# Protoboard_MX2-7-6-Terminal.net
KiCad netlist of a schematic drawn in EAGLE
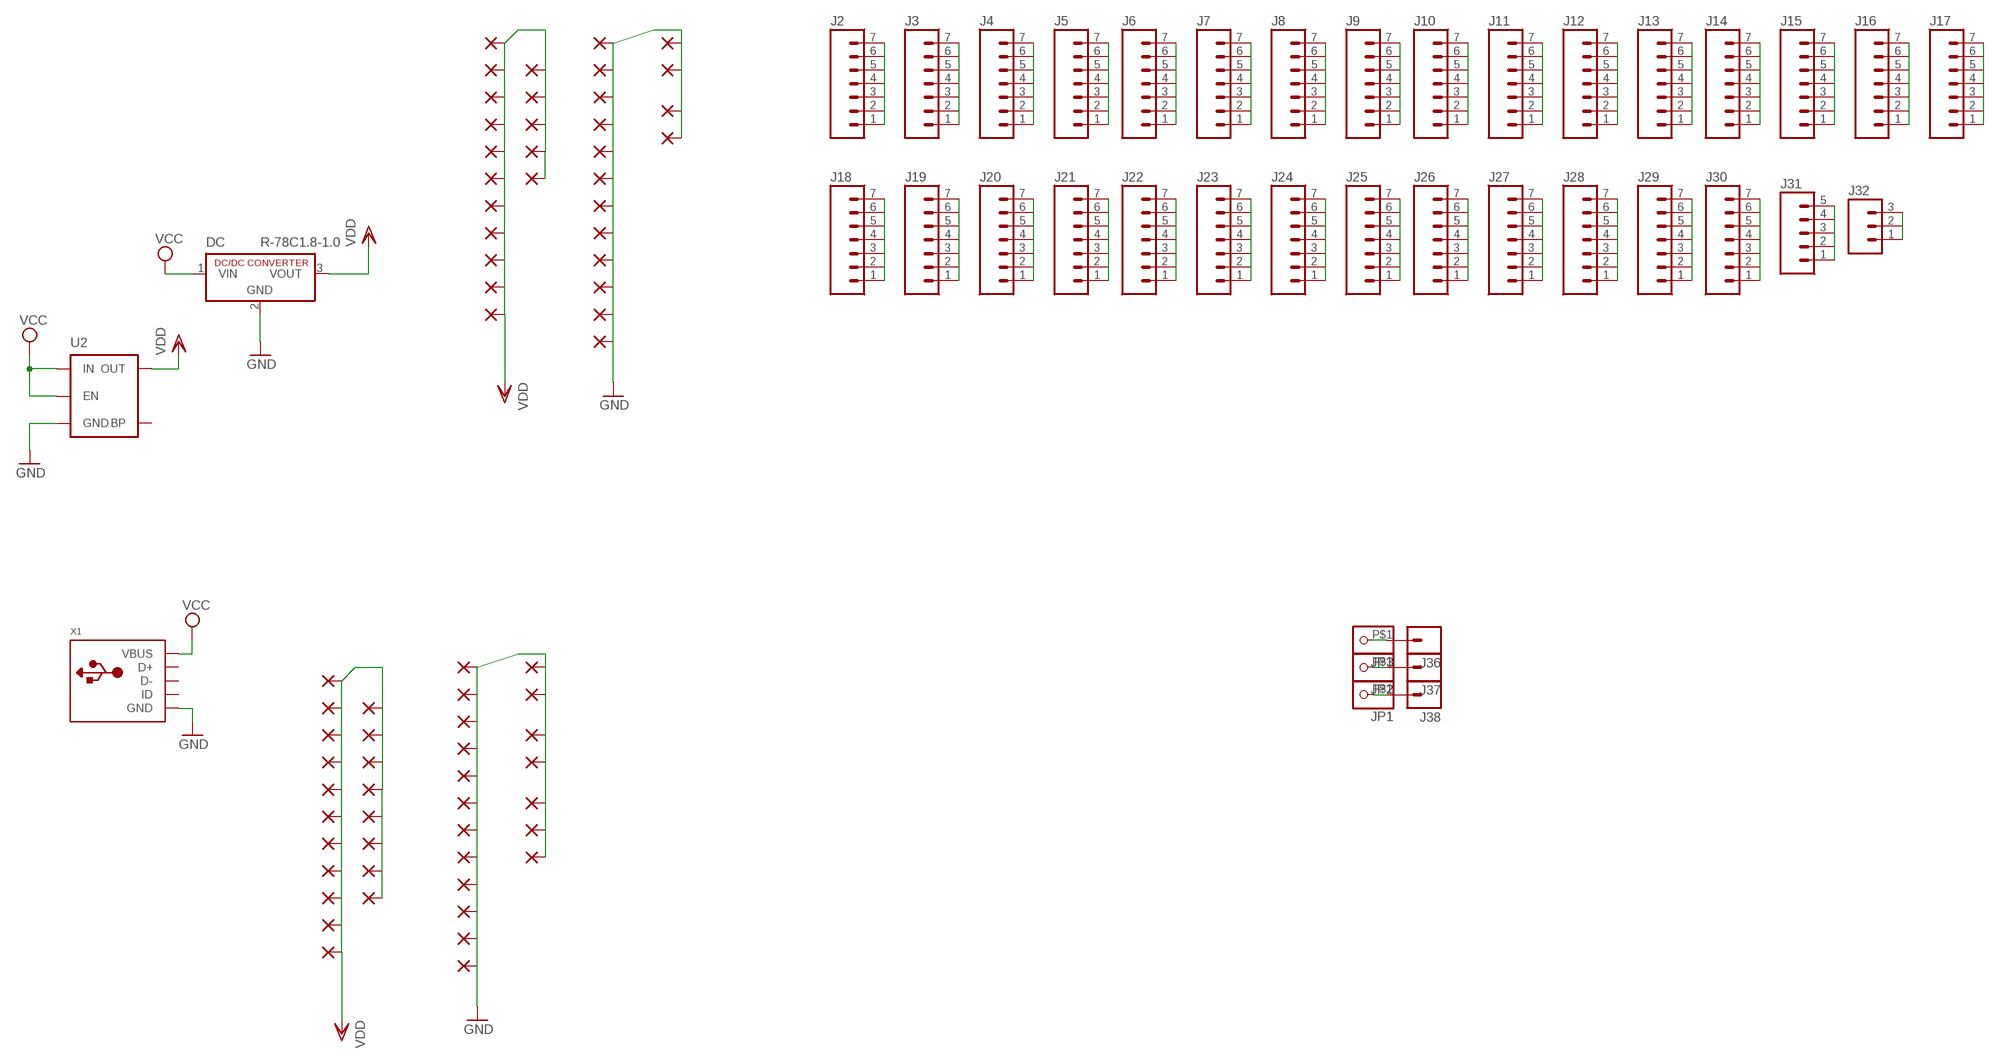
[diagram p0: schematic, sheet 1]

(export (version "E")
  (design (tool "Eeschema 10.0.6"))
  (components
    (comp (ref "DC")
      (value "R-78C1.8-1.0")
      (footprint "eagle-import:SIP3")
      (libsource (lib "eagle-import") (part "R-78C-1.01.8"))
    )
    (comp (ref "J2")
      (value "M07NO_SILK")
      (footprint "eagle-import:1X07_NO_SILK")
      (libsource (lib "eagle-import") (part "M07NO_SILK"))
    )
    (comp (ref "J3")
      (value "M07NO_SILK")
      (footprint "eagle-import:1X07_NO_SILK")
      (libsource (lib "eagle-import") (part "M07NO_SILK"))
    )
    (comp (ref "J4")
      (value "M07NO_SILK")
      (footprint "eagle-import:1X07_NO_SILK")
      (libsource (lib "eagle-import") (part "M07NO_SILK"))
    )
    (comp (ref "J5")
      (value "M07NO_SILK")
      (footprint "eagle-import:1X07_NO_SILK")
      (libsource (lib "eagle-import") (part "M07NO_SILK"))
    )
    (comp (ref "J6")
      (value "M07NO_SILK")
      (footprint "eagle-import:1X07_NO_SILK")
      (libsource (lib "eagle-import") (part "M07NO_SILK"))
    )
    (comp (ref "J7")
      (value "M07NO_SILK")
      (footprint "eagle-import:1X07_NO_SILK")
      (libsource (lib "eagle-import") (part "M07NO_SILK"))
    )
    (comp (ref "J8")
      (value "M07NO_SILK")
      (footprint "eagle-import:1X07_NO_SILK")
      (libsource (lib "eagle-import") (part "M07NO_SILK"))
    )
    (comp (ref "J9")
      (value "M07NO_SILK")
      (footprint "eagle-import:1X07_NO_SILK")
      (libsource (lib "eagle-import") (part "M07NO_SILK"))
    )
    (comp (ref "J10")
      (value "M07NO_SILK")
      (footprint "eagle-import:1X07_NO_SILK")
      (libsource (lib "eagle-import") (part "M07NO_SILK"))
    )
    (comp (ref "J11")
      (value "M07NO_SILK")
      (footprint "eagle-import:1X07_NO_SILK")
      (libsource (lib "eagle-import") (part "M07NO_SILK"))
    )
    (comp (ref "J12")
      (value "M07NO_SILK")
      (footprint "eagle-import:1X07_NO_SILK")
      (libsource (lib "eagle-import") (part "M07NO_SILK"))
    )
    (comp (ref "J13")
      (value "M07NO_SILK")
      (footprint "eagle-import:1X07_NO_SILK")
      (libsource (lib "eagle-import") (part "M07NO_SILK"))
    )
    (comp (ref "J14")
      (value "M07NO_SILK")
      (footprint "eagle-import:1X07_NO_SILK")
      (libsource (lib "eagle-import") (part "M07NO_SILK"))
    )
    (comp (ref "J15")
      (value "M07NO_SILK")
      (footprint "eagle-import:1X07_NO_SILK")
      (libsource (lib "eagle-import") (part "M07NO_SILK"))
    )
    (comp (ref "J16")
      (value "M07NO_SILK")
      (footprint "eagle-import:1X07_NO_SILK")
      (libsource (lib "eagle-import") (part "M07NO_SILK"))
    )
    (comp (ref "J17")
      (value "M07NO_SILK")
      (footprint "eagle-import:1X07_NO_SILK")
      (libsource (lib "eagle-import") (part "M07NO_SILK"))
    )
    (comp (ref "J18")
      (value "M07NO_SILK")
      (footprint "eagle-import:1X07_NO_SILK")
      (libsource (lib "eagle-import") (part "M07NO_SILK"))
    )
    (comp (ref "J19")
      (value "M07NO_SILK")
      (footprint "eagle-import:1X07_NO_SILK")
      (libsource (lib "eagle-import") (part "M07NO_SILK"))
    )
    (comp (ref "J20")
      (value "M07NO_SILK")
      (footprint "eagle-import:1X07_NO_SILK")
      (libsource (lib "eagle-import") (part "M07NO_SILK"))
    )
    (comp (ref "J21")
      (value "M07NO_SILK")
      (footprint "eagle-import:1X07_NO_SILK")
      (libsource (lib "eagle-import") (part "M07NO_SILK"))
    )
    (comp (ref "J22")
      (value "M07NO_SILK")
      (footprint "eagle-import:1X07_NO_SILK")
      (libsource (lib "eagle-import") (part "M07NO_SILK"))
    )
    (comp (ref "J23")
      (value "M07NO_SILK")
      (footprint "eagle-import:1X07_NO_SILK")
      (libsource (lib "eagle-import") (part "M07NO_SILK"))
    )
    (comp (ref "J24")
      (value "M07NO_SILK")
      (footprint "eagle-import:1X07_NO_SILK")
      (libsource (lib "eagle-import") (part "M07NO_SILK"))
    )
    (comp (ref "J25")
      (value "M07NO_SILK")
      (footprint "eagle-import:1X07_NO_SILK")
      (libsource (lib "eagle-import") (part "M07NO_SILK"))
    )
    (comp (ref "J26")
      (value "M07NO_SILK")
      (footprint "eagle-import:1X07_NO_SILK")
      (libsource (lib "eagle-import") (part "M07NO_SILK"))
    )
    (comp (ref "J27")
      (value "M07NO_SILK")
      (footprint "eagle-import:1X07_NO_SILK")
      (libsource (lib "eagle-import") (part "M07NO_SILK"))
    )
    (comp (ref "J28")
      (value "M07NO_SILK")
      (footprint "eagle-import:1X07_NO_SILK")
      (libsource (lib "eagle-import") (part "M07NO_SILK"))
    )
    (comp (ref "J29")
      (value "M07NO_SILK")
      (footprint "eagle-import:1X07_NO_SILK")
      (libsource (lib "eagle-import") (part "M07NO_SILK"))
    )
    (comp (ref "J30")
      (value "M07NO_SILK")
      (footprint "eagle-import:1X07_NO_SILK")
      (libsource (lib "eagle-import") (part "M07NO_SILK"))
    )
    (comp (ref "J31")
      (value "M05NO_SILK")
      (footprint "eagle-import:1X05_NO_SILK")
      (libsource (lib "eagle-import") (part "M05NO_SILK"))
    )
    (comp (ref "J32")
      (value "M031X03_NO_SILK")
      (footprint "eagle-import:1X03_NO_SILK")
      (libsource (lib "eagle-import") (part "M031X03_NO_SILK"))
    )
    (comp (ref "J36")
      (value "M01PTH_NO_SILK_YES_STOP")
      (footprint "eagle-import:1X01_NO_SILK")
      (libsource (lib "eagle-import") (part "M01PTH_NO_SILK_YES_STOP"))
    )
    (comp (ref "J37")
      (value "M01PTH_NO_SILK_YES_STOP")
      (footprint "eagle-import:1X01_NO_SILK")
      (libsource (lib "eagle-import") (part "M01PTH_NO_SILK_YES_STOP"))
    )
    (comp (ref "J38")
      (value "M01PTH_NO_SILK_YES_STOP")
      (footprint "eagle-import:1X01_NO_SILK")
      (libsource (lib "eagle-import") (part "M01PTH_NO_SILK_YES_STOP"))
    )
    (comp (ref "JP1")
      (value "PINHD-1X1-BIGPOGO")
      (footprint "eagle-import:1X1-BIGPOGO")
      (libsource (lib "eagle-import") (part "PINHD-1X1-BIGPOGO"))
    )
    (comp (ref "JP2")
      (value "PINHD-1X1-BIGPOGO")
      (footprint "eagle-import:1X1-BIGPOGO")
      (libsource (lib "eagle-import") (part "PINHD-1X1-BIGPOGO"))
    )
    (comp (ref "JP3")
      (value "PINHD-1X1-BIGPOGO")
      (footprint "eagle-import:1X1-BIGPOGO")
      (libsource (lib "eagle-import") (part "PINHD-1X1-BIGPOGO"))
    )
    (comp (ref "PAD4")
      (value "1,6/0,8")
      (footprint "eagle-import:1,6_0,8")
      (libsource (lib "eagle-import") (part "1,6/0,8"))
    )
    (comp (ref "PAD5")
      (value "1,6/0,8")
      (footprint "eagle-import:1,6_0,8")
      (libsource (lib "eagle-import") (part "1,6/0,8"))
    )
    (comp (ref "PAD6")
      (value "1,6/0,8")
      (footprint "eagle-import:1,6_0,8")
      (libsource (lib "eagle-import") (part "1,6/0,8"))
    )
    (comp (ref "PAD7")
      (value "1,6/0,8")
      (footprint "eagle-import:1,6_0,8")
      (libsource (lib "eagle-import") (part "1,6/0,8"))
    )
    (comp (ref "PAD8")
      (value "1,6/0,8")
      (footprint "eagle-import:1,6_0,8")
      (libsource (lib "eagle-import") (part "1,6/0,8"))
    )
    (comp (ref "PAD9")
      (value "1,6/0,8")
      (footprint "eagle-import:1,6_0,8")
      (libsource (lib "eagle-import") (part "1,6/0,8"))
    )
    (comp (ref "PAD10")
      (value "1,6/0,8")
      (footprint "eagle-import:1,6_0,8")
      (libsource (lib "eagle-import") (part "1,6/0,8"))
    )
    (comp (ref "PAD11")
      (value "1,6/0,8")
      (footprint "eagle-import:1,6_0,8")
      (libsource (lib "eagle-import") (part "1,6/0,8"))
    )
    (comp (ref "PAD12")
      (value "1,6/0,8")
      (footprint "eagle-import:1,6_0,8")
      (libsource (lib "eagle-import") (part "1,6/0,8"))
    )
    (comp (ref "PAD13")
      (value "1,6/0,8")
      (footprint "eagle-import:1,6_0,8")
      (libsource (lib "eagle-import") (part "1,6/0,8"))
    )
    (comp (ref "PAD14")
      (value "1,6/0,8")
      (footprint "eagle-import:1,6_0,8")
      (libsource (lib "eagle-import") (part "1,6/0,8"))
    )
    (comp (ref "PAD15")
      (value "1,6/0,8")
      (footprint "eagle-import:1,6_0,8")
      (libsource (lib "eagle-import") (part "1,6/0,8"))
    )
    (comp (ref "PAD16")
      (value "1,6/0,8")
      (footprint "eagle-import:1,6_0,8")
      (libsource (lib "eagle-import") (part "1,6/0,8"))
    )
    (comp (ref "PAD17")
      (value "1,6/0,8")
      (footprint "eagle-import:1,6_0,8")
      (libsource (lib "eagle-import") (part "1,6/0,8"))
    )
    (comp (ref "PAD18")
      (value "1,6/0,8")
      (footprint "eagle-import:1,6_0,8")
      (libsource (lib "eagle-import") (part "1,6/0,8"))
    )
    (comp (ref "PAD19")
      (value "1,6/0,8")
      (footprint "eagle-import:1,6_0,8")
      (libsource (lib "eagle-import") (part "1,6/0,8"))
    )
    (comp (ref "PAD20")
      (value "1,6/0,8")
      (footprint "eagle-import:1,6_0,8")
      (libsource (lib "eagle-import") (part "1,6/0,8"))
    )
    (comp (ref "PAD21")
      (value "1,6/0,8")
      (footprint "eagle-import:1,6_0,8")
      (libsource (lib "eagle-import") (part "1,6/0,8"))
    )
    (comp (ref "PAD22")
      (value "1,6/0,8")
      (footprint "eagle-import:1,6_0,8")
      (libsource (lib "eagle-import") (part "1,6/0,8"))
    )
    (comp (ref "PAD23")
      (value "1,6/0,8")
      (footprint "eagle-import:1,6_0,8")
      (libsource (lib "eagle-import") (part "1,6/0,8"))
    )
    (comp (ref "PAD24")
      (value "1,6/0,8")
      (footprint "eagle-import:1,6_0,8")
      (libsource (lib "eagle-import") (part "1,6/0,8"))
    )
    (comp (ref "PAD25")
      (value "1,6/0,8")
      (footprint "eagle-import:1,6_0,8")
      (libsource (lib "eagle-import") (part "1,6/0,8"))
    )
    (comp (ref "PAD26")
      (value "1,6/0,8")
      (footprint "eagle-import:1,6_0,8")
      (libsource (lib "eagle-import") (part "1,6/0,8"))
    )
    (comp (ref "PAD27")
      (value "1,6/0,8")
      (footprint "eagle-import:1,6_0,8")
      (libsource (lib "eagle-import") (part "1,6/0,8"))
    )
    (comp (ref "PAD28")
      (value "1,6/0,8")
      (footprint "eagle-import:1,6_0,8")
      (libsource (lib "eagle-import") (part "1,6/0,8"))
    )
    (comp (ref "PAD29")
      (value "1,6/0,8")
      (footprint "eagle-import:1,6_0,8")
      (libsource (lib "eagle-import") (part "1,6/0,8"))
    )
    (comp (ref "PAD30")
      (value "1,6/0,8")
      (footprint "eagle-import:1,6_0,8")
      (libsource (lib "eagle-import") (part "1,6/0,8"))
    )
    (comp (ref "PAD31")
      (value "1,6/0,8")
      (footprint "eagle-import:1,6_0,8")
      (libsource (lib "eagle-import") (part "1,6/0,8"))
    )
    (comp (ref "PAD32")
      (value "1,6/0,8")
      (footprint "eagle-import:1,6_0,8")
      (libsource (lib "eagle-import") (part "1,6/0,8"))
    )
    (comp (ref "PAD33")
      (value "1,6/0,8")
      (footprint "eagle-import:1,6_0,8")
      (libsource (lib "eagle-import") (part "1,6/0,8"))
    )
    (comp (ref "PAD36")
      (value "1,6/0,8")
      (footprint "eagle-import:1,6_0,8")
      (libsource (lib "eagle-import") (part "1,6/0,8"))
    )
    (comp (ref "PAD38")
      (value "1,6/0,8")
      (footprint "eagle-import:1,6_0,8")
      (libsource (lib "eagle-import") (part "1,6/0,8"))
    )
    (comp (ref "PAD421")
      (value "1,6/0,8")
      (footprint "eagle-import:1,6_0,8")
      (libsource (lib "eagle-import") (part "1,6/0,8"))
    )
    (comp (ref "PAD422")
      (value "1,6/0,8")
      (footprint "eagle-import:1,6_0,8")
      (libsource (lib "eagle-import") (part "1,6/0,8"))
    )
    (comp (ref "PAD423")
      (value "1,6/0,8")
      (footprint "eagle-import:1,6_0,8")
      (libsource (lib "eagle-import") (part "1,6/0,8"))
    )
    (comp (ref "PAD424")
      (value "1,6/0,8")
      (footprint "eagle-import:1,6_0,8")
      (libsource (lib "eagle-import") (part "1,6/0,8"))
    )
    (comp (ref "PAD425")
      (value "1,6/0,8")
      (footprint "eagle-import:1,6_0,8")
      (libsource (lib "eagle-import") (part "1,6/0,8"))
    )
    (comp (ref "PAD426")
      (value "1,6/0,8")
      (footprint "eagle-import:1,6_0,8")
      (libsource (lib "eagle-import") (part "1,6/0,8"))
    )
    (comp (ref "PAD427")
      (value "1,6/0,8")
      (footprint "eagle-import:1,6_0,8")
      (libsource (lib "eagle-import") (part "1,6/0,8"))
    )
    (comp (ref "PAD428")
      (value "1,6/0,8")
      (footprint "eagle-import:1,6_0,8")
      (libsource (lib "eagle-import") (part "1,6/0,8"))
    )
    (comp (ref "PAD429")
      (value "1,6/0,8")
      (footprint "eagle-import:1,6_0,8")
      (libsource (lib "eagle-import") (part "1,6/0,8"))
    )
    (comp (ref "PAD430")
      (value "1,6/0,8")
      (footprint "eagle-import:1,6_0,8")
      (libsource (lib "eagle-import") (part "1,6/0,8"))
    )
    (comp (ref "PAD431")
      (value "1,6/0,8")
      (footprint "eagle-import:1,6_0,8")
      (libsource (lib "eagle-import") (part "1,6/0,8"))
    )
    (comp (ref "PAD432")
      (value "1,6/0,8")
      (footprint "eagle-import:1,6_0,8")
      (libsource (lib "eagle-import") (part "1,6/0,8"))
    )
    (comp (ref "PAD433")
      (value "1,6/0,8")
      (footprint "eagle-import:1,6_0,8")
      (libsource (lib "eagle-import") (part "1,6/0,8"))
    )
    (comp (ref "PAD434")
      (value "1,6/0,8")
      (footprint "eagle-import:1,6_0,8")
      (libsource (lib "eagle-import") (part "1,6/0,8"))
    )
    (comp (ref "PAD435")
      (value "1,6/0,8")
      (footprint "eagle-import:1,6_0,8")
      (libsource (lib "eagle-import") (part "1,6/0,8"))
    )
    (comp (ref "PAD436")
      (value "1,6/0,8")
      (footprint "eagle-import:1,6_0,8")
      (libsource (lib "eagle-import") (part "1,6/0,8"))
    )
    (comp (ref "PAD439")
      (value "1,6/0,8")
      (footprint "eagle-import:1,6_0,8")
      (libsource (lib "eagle-import") (part "1,6/0,8"))
    )
    (comp (ref "PAD440")
      (value "1,6/0,8")
      (footprint "eagle-import:1,6_0,8")
      (libsource (lib "eagle-import") (part "1,6/0,8"))
    )
    (comp (ref "PAD441")
      (value "1,6/0,8")
      (footprint "eagle-import:1,6_0,8")
      (libsource (lib "eagle-import") (part "1,6/0,8"))
    )
    (comp (ref "PAD442")
      (value "1,6/0,8")
      (footprint "eagle-import:1,6_0,8")
      (libsource (lib "eagle-import") (part "1,6/0,8"))
    )
    (comp (ref "PAD443")
      (value "1,6/0,8")
      (footprint "eagle-import:1,6_0,8")
      (libsource (lib "eagle-import") (part "1,6/0,8"))
    )
    (comp (ref "PAD444")
      (value "1,6/0,8")
      (footprint "eagle-import:1,6_0,8")
      (libsource (lib "eagle-import") (part "1,6/0,8"))
    )
    (comp (ref "PAD445")
      (value "1,6/0,8")
      (footprint "eagle-import:1,6_0,8")
      (libsource (lib "eagle-import") (part "1,6/0,8"))
    )
    (comp (ref "PAD446")
      (value "1,6/0,8")
      (footprint "eagle-import:1,6_0,8")
      (libsource (lib "eagle-import") (part "1,6/0,8"))
    )
    (comp (ref "PAD447")
      (value "1,6/0,8")
      (footprint "eagle-import:1,6_0,8")
      (libsource (lib "eagle-import") (part "1,6/0,8"))
    )
    (comp (ref "PAD448")
      (value "1,6/0,8")
      (footprint "eagle-import:1,6_0,8")
      (libsource (lib "eagle-import") (part "1,6/0,8"))
    )
    (comp (ref "PAD449")
      (value "1,6/0,8")
      (footprint "eagle-import:1,6_0,8")
      (libsource (lib "eagle-import") (part "1,6/0,8"))
    )
    (comp (ref "PAD450")
      (value "1,6/0,8")
      (footprint "eagle-import:1,6_0,8")
      (libsource (lib "eagle-import") (part "1,6/0,8"))
    )
    (comp (ref "PAD451")
      (value "1,6/0,8")
      (footprint "eagle-import:1,6_0,8")
      (libsource (lib "eagle-import") (part "1,6/0,8"))
    )
    (comp (ref "PAD452")
      (value "1,6/0,8")
      (footprint "eagle-import:1,6_0,8")
      (libsource (lib "eagle-import") (part "1,6/0,8"))
    )
    (comp (ref "PAD453")
      (value "1,6/0,8")
      (footprint "eagle-import:1,6_0,8")
      (libsource (lib "eagle-import") (part "1,6/0,8"))
    )
    (comp (ref "PAD454")
      (value "1,6/0,8")
      (footprint "eagle-import:1,6_0,8")
      (libsource (lib "eagle-import") (part "1,6/0,8"))
    )
    (comp (ref "PAD455")
      (value "1,6/0,8")
      (footprint "eagle-import:1,6_0,8")
      (libsource (lib "eagle-import") (part "1,6/0,8"))
    )
    (comp (ref "PAD456")
      (value "1,6/0,8")
      (footprint "eagle-import:1,6_0,8")
      (libsource (lib "eagle-import") (part "1,6/0,8"))
    )
    (comp (ref "PAD459")
      (value "1,6/0,8")
      (footprint "eagle-import:1,6_0,8")
      (libsource (lib "eagle-import") (part "1,6/0,8"))
    )
    (comp (ref "PAD460")
      (value "1,6/0,8")
      (footprint "eagle-import:1,6_0,8")
      (libsource (lib "eagle-import") (part "1,6/0,8"))
    )
    (comp (ref "PAD461")
      (value "1,6/0,8")
      (footprint "eagle-import:1,6_0,8")
      (libsource (lib "eagle-import") (part "1,6/0,8"))
    )
    (comp (ref "PAD462")
      (value "1,6/0,8")
      (footprint "eagle-import:1,6_0,8")
      (libsource (lib "eagle-import") (part "1,6/0,8"))
    )
    (comp (ref "U2")
      (value "MIC52053.3V")
      (footprint "eagle-import:SOT23-5")
      (libsource (lib "eagle-import") (part "MIC52053.3V"))
    )
    (comp (ref "X1")
      (value "USBMICRO_20329")
      (footprint "eagle-import:4UCONN_20329")
      (libsource (lib "eagle-import") (part "USBMICRO_20329"))
    )
  )
  (nets
    (net (code "1") (name "GND") (class "Default")
      (node (ref "DC") (pin "2") (pinfunction "GND_2") (pintype "passive"))
      (node (ref "PAD17") (pin "1") (pinfunction "P_1") (pintype "passive"))
      (node (ref "PAD22") (pin "1") (pinfunction "P_1") (pintype "passive"))
      (node (ref "PAD23") (pin "1") (pinfunction "P_1") (pintype "passive"))
      (node (ref "PAD24") (pin "1") (pinfunction "P_1") (pintype "passive"))
      (node (ref "PAD25") (pin "1") (pinfunction "P_1") (pintype "passive"))
      (node (ref "PAD26") (pin "1") (pinfunction "P_1") (pintype "passive"))
      (node (ref "PAD27") (pin "1") (pinfunction "P_1") (pintype "passive"))
      (node (ref "PAD28") (pin "1") (pinfunction "P_1") (pintype "passive"))
      (node (ref "PAD29") (pin "1") (pinfunction "P_1") (pintype "passive"))
      (node (ref "PAD30") (pin "1") (pinfunction "P_1") (pintype "passive"))
      (node (ref "PAD31") (pin "1") (pinfunction "P_1") (pintype "passive"))
      (node (ref "PAD32") (pin "1") (pinfunction "P_1") (pintype "passive"))
      (node (ref "PAD33") (pin "1") (pinfunction "P_1") (pintype "passive"))
      (node (ref "PAD36") (pin "1") (pinfunction "P_1") (pintype "passive"))
      (node (ref "PAD38") (pin "1") (pinfunction "P_1") (pintype "passive"))
      (node (ref "PAD4") (pin "1") (pinfunction "P_1") (pintype "passive"))
      (node (ref "PAD421") (pin "1") (pinfunction "P_1") (pintype "passive"))
      (node (ref "PAD422") (pin "1") (pinfunction "P_1") (pintype "passive"))
      (node (ref "PAD423") (pin "1") (pinfunction "P_1") (pintype "passive"))
      (node (ref "PAD424") (pin "1") (pinfunction "P_1") (pintype "passive"))
      (node (ref "PAD425") (pin "1") (pinfunction "P_1") (pintype "passive"))
      (node (ref "PAD426") (pin "1") (pinfunction "P_1") (pintype "passive"))
      (node (ref "PAD427") (pin "1") (pinfunction "P_1") (pintype "passive"))
      (node (ref "PAD428") (pin "1") (pinfunction "P_1") (pintype "passive"))
      (node (ref "PAD429") (pin "1") (pinfunction "P_1") (pintype "passive"))
      (node (ref "PAD430") (pin "1") (pinfunction "P_1") (pintype "passive"))
      (node (ref "PAD431") (pin "1") (pinfunction "P_1") (pintype "passive"))
      (node (ref "PAD432") (pin "1") (pinfunction "P_1") (pintype "passive"))
      (node (ref "PAD433") (pin "1") (pinfunction "P_1") (pintype "passive"))
      (node (ref "PAD434") (pin "1") (pinfunction "P_1") (pintype "passive"))
      (node (ref "PAD435") (pin "1") (pinfunction "P_1") (pintype "passive"))
      (node (ref "PAD436") (pin "1") (pinfunction "P_1") (pintype "passive"))
      (node (ref "PAD439") (pin "1") (pinfunction "P_1") (pintype "passive"))
      (node (ref "PAD440") (pin "1") (pinfunction "P_1") (pintype "passive"))
      (node (ref "PAD441") (pin "1") (pinfunction "P_1") (pintype "passive"))
      (node (ref "U2") (pin "2") (pinfunction "GND_2") (pintype "input"))
      (node (ref "X1") (pin "BASE@1") (pinfunction "GND_BASE@1") (pintype "power_in"))
      (node (ref "X1") (pin "BASE@2") (pinfunction "GND_BASE@2") (pintype "power_in"))
      (node (ref "X1") (pin "GND") (pinfunction "GND_GND") (pintype "power_in"))
      (node (ref "X1") (pin "SPRT@1") (pinfunction "GND_SPRT@1") (pintype "power_in"))
      (node (ref "X1") (pin "SPRT@2") (pinfunction "GND_SPRT@2") (pintype "power_in"))
      (node (ref "X1") (pin "SPRT@3") (pinfunction "GND_SPRT@3") (pintype "power_in"))
      (node (ref "X1") (pin "SPRT@4") (pinfunction "GND_SPRT@4") (pintype "power_in"))
    )
    (net (code "2") (name "Net-(J2-Pad1)") (class "Default")
      (node (ref "J2") (pin "1") (pinfunction "1_1") (pintype "passive"))
      (node (ref "J2") (pin "2") (pinfunction "2_2") (pintype "passive"))
      (node (ref "J2") (pin "3") (pinfunction "3_3") (pintype "passive"))
      (node (ref "J2") (pin "4") (pinfunction "4_4") (pintype "passive"))
      (node (ref "J2") (pin "5") (pinfunction "5_5") (pintype "passive"))
      (node (ref "J2") (pin "6") (pinfunction "6_6") (pintype "passive"))
      (node (ref "J2") (pin "7") (pinfunction "7_7") (pintype "passive"))
    )
    (net (code "3") (name "Net-(J3-Pad1)") (class "Default")
      (node (ref "J3") (pin "1") (pinfunction "1_1") (pintype "passive"))
      (node (ref "J3") (pin "2") (pinfunction "2_2") (pintype "passive"))
      (node (ref "J3") (pin "3") (pinfunction "3_3") (pintype "passive"))
      (node (ref "J3") (pin "4") (pinfunction "4_4") (pintype "passive"))
      (node (ref "J3") (pin "5") (pinfunction "5_5") (pintype "passive"))
      (node (ref "J3") (pin "6") (pinfunction "6_6") (pintype "passive"))
      (node (ref "J3") (pin "7") (pinfunction "7_7") (pintype "passive"))
    )
    (net (code "4") (name "Net-(J4-Pad1)") (class "Default")
      (node (ref "J4") (pin "1") (pinfunction "1_1") (pintype "passive"))
      (node (ref "J4") (pin "2") (pinfunction "2_2") (pintype "passive"))
      (node (ref "J4") (pin "3") (pinfunction "3_3") (pintype "passive"))
      (node (ref "J4") (pin "4") (pinfunction "4_4") (pintype "passive"))
      (node (ref "J4") (pin "5") (pinfunction "5_5") (pintype "passive"))
      (node (ref "J4") (pin "6") (pinfunction "6_6") (pintype "passive"))
      (node (ref "J4") (pin "7") (pinfunction "7_7") (pintype "passive"))
    )
    (net (code "5") (name "Net-(J5-Pad1)") (class "Default")
      (node (ref "J5") (pin "1") (pinfunction "1_1") (pintype "passive"))
      (node (ref "J5") (pin "2") (pinfunction "2_2") (pintype "passive"))
      (node (ref "J5") (pin "3") (pinfunction "3_3") (pintype "passive"))
      (node (ref "J5") (pin "4") (pinfunction "4_4") (pintype "passive"))
      (node (ref "J5") (pin "5") (pinfunction "5_5") (pintype "passive"))
      (node (ref "J5") (pin "6") (pinfunction "6_6") (pintype "passive"))
      (node (ref "J5") (pin "7") (pinfunction "7_7") (pintype "passive"))
    )
    (net (code "6") (name "Net-(J6-Pad1)") (class "Default")
      (node (ref "J6") (pin "1") (pinfunction "1_1") (pintype "passive"))
      (node (ref "J6") (pin "2") (pinfunction "2_2") (pintype "passive"))
      (node (ref "J6") (pin "3") (pinfunction "3_3") (pintype "passive"))
      (node (ref "J6") (pin "4") (pinfunction "4_4") (pintype "passive"))
      (node (ref "J6") (pin "5") (pinfunction "5_5") (pintype "passive"))
      (node (ref "J6") (pin "6") (pinfunction "6_6") (pintype "passive"))
      (node (ref "J6") (pin "7") (pinfunction "7_7") (pintype "passive"))
    )
    (net (code "7") (name "Net-(J7-Pad1)") (class "Default")
      (node (ref "J7") (pin "1") (pinfunction "1_1") (pintype "passive"))
      (node (ref "J7") (pin "2") (pinfunction "2_2") (pintype "passive"))
      (node (ref "J7") (pin "3") (pinfunction "3_3") (pintype "passive"))
      (node (ref "J7") (pin "4") (pinfunction "4_4") (pintype "passive"))
      (node (ref "J7") (pin "5") (pinfunction "5_5") (pintype "passive"))
      (node (ref "J7") (pin "6") (pinfunction "6_6") (pintype "passive"))
      (node (ref "J7") (pin "7") (pinfunction "7_7") (pintype "passive"))
    )
    (net (code "8") (name "Net-(J8-Pad1)") (class "Default")
      (node (ref "J8") (pin "1") (pinfunction "1_1") (pintype "passive"))
      (node (ref "J8") (pin "2") (pinfunction "2_2") (pintype "passive"))
      (node (ref "J8") (pin "3") (pinfunction "3_3") (pintype "passive"))
      (node (ref "J8") (pin "4") (pinfunction "4_4") (pintype "passive"))
      (node (ref "J8") (pin "5") (pinfunction "5_5") (pintype "passive"))
      (node (ref "J8") (pin "6") (pinfunction "6_6") (pintype "passive"))
      (node (ref "J8") (pin "7") (pinfunction "7_7") (pintype "passive"))
    )
    (net (code "9") (name "Net-(J9-Pad1)") (class "Default")
      (node (ref "J9") (pin "1") (pinfunction "1_1") (pintype "passive"))
      (node (ref "J9") (pin "2") (pinfunction "2_2") (pintype "passive"))
      (node (ref "J9") (pin "3") (pinfunction "3_3") (pintype "passive"))
      (node (ref "J9") (pin "4") (pinfunction "4_4") (pintype "passive"))
      (node (ref "J9") (pin "5") (pinfunction "5_5") (pintype "passive"))
      (node (ref "J9") (pin "6") (pinfunction "6_6") (pintype "passive"))
      (node (ref "J9") (pin "7") (pinfunction "7_7") (pintype "passive"))
    )
    (net (code "10") (name "Net-(J10-Pad1)") (class "Default")
      (node (ref "J10") (pin "1") (pinfunction "1_1") (pintype "passive"))
      (node (ref "J10") (pin "2") (pinfunction "2_2") (pintype "passive"))
      (node (ref "J10") (pin "3") (pinfunction "3_3") (pintype "passive"))
      (node (ref "J10") (pin "4") (pinfunction "4_4") (pintype "passive"))
      (node (ref "J10") (pin "5") (pinfunction "5_5") (pintype "passive"))
      (node (ref "J10") (pin "6") (pinfunction "6_6") (pintype "passive"))
      (node (ref "J10") (pin "7") (pinfunction "7_7") (pintype "passive"))
    )
    (net (code "11") (name "Net-(J11-Pad1)") (class "Default")
      (node (ref "J11") (pin "1") (pinfunction "1_1") (pintype "passive"))
      (node (ref "J11") (pin "2") (pinfunction "2_2") (pintype "passive"))
      (node (ref "J11") (pin "3") (pinfunction "3_3") (pintype "passive"))
      (node (ref "J11") (pin "4") (pinfunction "4_4") (pintype "passive"))
      (node (ref "J11") (pin "5") (pinfunction "5_5") (pintype "passive"))
      (node (ref "J11") (pin "6") (pinfunction "6_6") (pintype "passive"))
      (node (ref "J11") (pin "7") (pinfunction "7_7") (pintype "passive"))
    )
    (net (code "12") (name "Net-(J12-Pad1)") (class "Default")
      (node (ref "J12") (pin "1") (pinfunction "1_1") (pintype "passive"))
      (node (ref "J12") (pin "2") (pinfunction "2_2") (pintype "passive"))
      (node (ref "J12") (pin "3") (pinfunction "3_3") (pintype "passive"))
      (node (ref "J12") (pin "4") (pinfunction "4_4") (pintype "passive"))
      (node (ref "J12") (pin "5") (pinfunction "5_5") (pintype "passive"))
      (node (ref "J12") (pin "6") (pinfunction "6_6") (pintype "passive"))
      (node (ref "J12") (pin "7") (pinfunction "7_7") (pintype "passive"))
    )
    (net (code "13") (name "Net-(J13-Pad1)") (class "Default")
      (node (ref "J13") (pin "1") (pinfunction "1_1") (pintype "passive"))
      (node (ref "J13") (pin "2") (pinfunction "2_2") (pintype "passive"))
      (node (ref "J13") (pin "3") (pinfunction "3_3") (pintype "passive"))
      (node (ref "J13") (pin "4") (pinfunction "4_4") (pintype "passive"))
      (node (ref "J13") (pin "5") (pinfunction "5_5") (pintype "passive"))
      (node (ref "J13") (pin "6") (pinfunction "6_6") (pintype "passive"))
      (node (ref "J13") (pin "7") (pinfunction "7_7") (pintype "passive"))
    )
    (net (code "14") (name "Net-(J14-Pad1)") (class "Default")
      (node (ref "J14") (pin "1") (pinfunction "1_1") (pintype "passive"))
      (node (ref "J14") (pin "2") (pinfunction "2_2") (pintype "passive"))
      (node (ref "J14") (pin "3") (pinfunction "3_3") (pintype "passive"))
      (node (ref "J14") (pin "4") (pinfunction "4_4") (pintype "passive"))
      (node (ref "J14") (pin "5") (pinfunction "5_5") (pintype "passive"))
      (node (ref "J14") (pin "6") (pinfunction "6_6") (pintype "passive"))
      (node (ref "J14") (pin "7") (pinfunction "7_7") (pintype "passive"))
    )
    (net (code "15") (name "Net-(J15-Pad1)") (class "Default")
      (node (ref "J15") (pin "1") (pinfunction "1_1") (pintype "passive"))
      (node (ref "J15") (pin "2") (pinfunction "2_2") (pintype "passive"))
      (node (ref "J15") (pin "3") (pinfunction "3_3") (pintype "passive"))
      (node (ref "J15") (pin "4") (pinfunction "4_4") (pintype "passive"))
      (node (ref "J15") (pin "5") (pinfunction "5_5") (pintype "passive"))
      (node (ref "J15") (pin "6") (pinfunction "6_6") (pintype "passive"))
      (node (ref "J15") (pin "7") (pinfunction "7_7") (pintype "passive"))
    )
    (net (code "16") (name "Net-(J16-Pad1)") (class "Default")
      (node (ref "J16") (pin "1") (pinfunction "1_1") (pintype "passive"))
      (node (ref "J16") (pin "2") (pinfunction "2_2") (pintype "passive"))
      (node (ref "J16") (pin "3") (pinfunction "3_3") (pintype "passive"))
      (node (ref "J16") (pin "4") (pinfunction "4_4") (pintype "passive"))
      (node (ref "J16") (pin "5") (pinfunction "5_5") (pintype "passive"))
      (node (ref "J16") (pin "6") (pinfunction "6_6") (pintype "passive"))
      (node (ref "J16") (pin "7") (pinfunction "7_7") (pintype "passive"))
    )
    (net (code "17") (name "Net-(J17-Pad1)") (class "Default")
      (node (ref "J17") (pin "1") (pinfunction "1_1") (pintype "passive"))
      (node (ref "J17") (pin "2") (pinfunction "2_2") (pintype "passive"))
      (node (ref "J17") (pin "3") (pinfunction "3_3") (pintype "passive"))
      (node (ref "J17") (pin "4") (pinfunction "4_4") (pintype "passive"))
      (node (ref "J17") (pin "5") (pinfunction "5_5") (pintype "passive"))
      (node (ref "J17") (pin "6") (pinfunction "6_6") (pintype "passive"))
      (node (ref "J17") (pin "7") (pinfunction "7_7") (pintype "passive"))
    )
    (net (code "18") (name "Net-(J18-Pad1)") (class "Default")
      (node (ref "J18") (pin "1") (pinfunction "1_1") (pintype "passive"))
      (node (ref "J18") (pin "2") (pinfunction "2_2") (pintype "passive"))
      (node (ref "J18") (pin "3") (pinfunction "3_3") (pintype "passive"))
      (node (ref "J18") (pin "4") (pinfunction "4_4") (pintype "passive"))
      (node (ref "J18") (pin "5") (pinfunction "5_5") (pintype "passive"))
      (node (ref "J18") (pin "6") (pinfunction "6_6") (pintype "passive"))
      (node (ref "J18") (pin "7") (pinfunction "7_7") (pintype "passive"))
    )
    (net (code "19") (name "Net-(J19-Pad1)") (class "Default")
      (node (ref "J19") (pin "1") (pinfunction "1_1") (pintype "passive"))
      (node (ref "J19") (pin "2") (pinfunction "2_2") (pintype "passive"))
      (node (ref "J19") (pin "3") (pinfunction "3_3") (pintype "passive"))
      (node (ref "J19") (pin "4") (pinfunction "4_4") (pintype "passive"))
      (node (ref "J19") (pin "5") (pinfunction "5_5") (pintype "passive"))
      (node (ref "J19") (pin "6") (pinfunction "6_6") (pintype "passive"))
      (node (ref "J19") (pin "7") (pinfunction "7_7") (pintype "passive"))
    )
    (net (code "20") (name "Net-(J20-Pad1)") (class "Default")
      (node (ref "J20") (pin "1") (pinfunction "1_1") (pintype "passive"))
      (node (ref "J20") (pin "2") (pinfunction "2_2") (pintype "passive"))
      (node (ref "J20") (pin "3") (pinfunction "3_3") (pintype "passive"))
      (node (ref "J20") (pin "4") (pinfunction "4_4") (pintype "passive"))
      (node (ref "J20") (pin "5") (pinfunction "5_5") (pintype "passive"))
      (node (ref "J20") (pin "6") (pinfunction "6_6") (pintype "passive"))
      (node (ref "J20") (pin "7") (pinfunction "7_7") (pintype "passive"))
    )
    (net (code "21") (name "Net-(J21-Pad1)") (class "Default")
      (node (ref "J21") (pin "1") (pinfunction "1_1") (pintype "passive"))
      (node (ref "J21") (pin "2") (pinfunction "2_2") (pintype "passive"))
      (node (ref "J21") (pin "3") (pinfunction "3_3") (pintype "passive"))
      (node (ref "J21") (pin "4") (pinfunction "4_4") (pintype "passive"))
      (node (ref "J21") (pin "5") (pinfunction "5_5") (pintype "passive"))
      (node (ref "J21") (pin "6") (pinfunction "6_6") (pintype "passive"))
      (node (ref "J21") (pin "7") (pinfunction "7_7") (pintype "passive"))
    )
    (net (code "22") (name "Net-(J22-Pad1)") (class "Default")
      (node (ref "J22") (pin "1") (pinfunction "1_1") (pintype "passive"))
      (node (ref "J22") (pin "2") (pinfunction "2_2") (pintype "passive"))
      (node (ref "J22") (pin "3") (pinfunction "3_3") (pintype "passive"))
      (node (ref "J22") (pin "4") (pinfunction "4_4") (pintype "passive"))
      (node (ref "J22") (pin "5") (pinfunction "5_5") (pintype "passive"))
      (node (ref "J22") (pin "6") (pinfunction "6_6") (pintype "passive"))
      (node (ref "J22") (pin "7") (pinfunction "7_7") (pintype "passive"))
    )
    (net (code "23") (name "Net-(J23-Pad1)") (class "Default")
      (node (ref "J23") (pin "1") (pinfunction "1_1") (pintype "passive"))
      (node (ref "J23") (pin "2") (pinfunction "2_2") (pintype "passive"))
      (node (ref "J23") (pin "3") (pinfunction "3_3") (pintype "passive"))
      (node (ref "J23") (pin "4") (pinfunction "4_4") (pintype "passive"))
      (node (ref "J23") (pin "5") (pinfunction "5_5") (pintype "passive"))
      (node (ref "J23") (pin "6") (pinfunction "6_6") (pintype "passive"))
      (node (ref "J23") (pin "7") (pinfunction "7_7") (pintype "passive"))
    )
    (net (code "24") (name "Net-(J24-Pad1)") (class "Default")
      (node (ref "J24") (pin "1") (pinfunction "1_1") (pintype "passive"))
      (node (ref "J24") (pin "2") (pinfunction "2_2") (pintype "passive"))
      (node (ref "J24") (pin "3") (pinfunction "3_3") (pintype "passive"))
      (node (ref "J24") (pin "4") (pinfunction "4_4") (pintype "passive"))
      (node (ref "J24") (pin "5") (pinfunction "5_5") (pintype "passive"))
      (node (ref "J24") (pin "6") (pinfunction "6_6") (pintype "passive"))
      (node (ref "J24") (pin "7") (pinfunction "7_7") (pintype "passive"))
    )
    (net (code "25") (name "Net-(J25-Pad1)") (class "Default")
      (node (ref "J25") (pin "1") (pinfunction "1_1") (pintype "passive"))
      (node (ref "J25") (pin "2") (pinfunction "2_2") (pintype "passive"))
      (node (ref "J25") (pin "3") (pinfunction "3_3") (pintype "passive"))
      (node (ref "J25") (pin "4") (pinfunction "4_4") (pintype "passive"))
      (node (ref "J25") (pin "5") (pinfunction "5_5") (pintype "passive"))
      (node (ref "J25") (pin "6") (pinfunction "6_6") (pintype "passive"))
      (node (ref "J25") (pin "7") (pinfunction "7_7") (pintype "passive"))
    )
    (net (code "26") (name "Net-(J26-Pad1)") (class "Default")
      (node (ref "J26") (pin "1") (pinfunction "1_1") (pintype "passive"))
      (node (ref "J26") (pin "2") (pinfunction "2_2") (pintype "passive"))
      (node (ref "J26") (pin "3") (pinfunction "3_3") (pintype "passive"))
      (node (ref "J26") (pin "4") (pinfunction "4_4") (pintype "passive"))
      (node (ref "J26") (pin "5") (pinfunction "5_5") (pintype "passive"))
      (node (ref "J26") (pin "6") (pinfunction "6_6") (pintype "passive"))
      (node (ref "J26") (pin "7") (pinfunction "7_7") (pintype "passive"))
    )
    (net (code "27") (name "Net-(J27-Pad1)") (class "Default")
      (node (ref "J27") (pin "1") (pinfunction "1_1") (pintype "passive"))
      (node (ref "J27") (pin "2") (pinfunction "2_2") (pintype "passive"))
      (node (ref "J27") (pin "3") (pinfunction "3_3") (pintype "passive"))
      (node (ref "J27") (pin "4") (pinfunction "4_4") (pintype "passive"))
      (node (ref "J27") (pin "5") (pinfunction "5_5") (pintype "passive"))
      (node (ref "J27") (pin "6") (pinfunction "6_6") (pintype "passive"))
      (node (ref "J27") (pin "7") (pinfunction "7_7") (pintype "passive"))
    )
    (net (code "28") (name "Net-(J28-Pad1)") (class "Default")
      (node (ref "J28") (pin "1") (pinfunction "1_1") (pintype "passive"))
      (node (ref "J28") (pin "2") (pinfunction "2_2") (pintype "passive"))
      (node (ref "J28") (pin "3") (pinfunction "3_3") (pintype "passive"))
      (node (ref "J28") (pin "4") (pinfunction "4_4") (pintype "passive"))
      (node (ref "J28") (pin "5") (pinfunction "5_5") (pintype "passive"))
      (node (ref "J28") (pin "6") (pinfunction "6_6") (pintype "passive"))
      (node (ref "J28") (pin "7") (pinfunction "7_7") (pintype "passive"))
    )
    (net (code "29") (name "Net-(J29-Pad1)") (class "Default")
      (node (ref "J29") (pin "1") (pinfunction "1_1") (pintype "passive"))
      (node (ref "J29") (pin "2") (pinfunction "2_2") (pintype "passive"))
      (node (ref "J29") (pin "3") (pinfunction "3_3") (pintype "passive"))
      (node (ref "J29") (pin "4") (pinfunction "4_4") (pintype "passive"))
      (node (ref "J29") (pin "5") (pinfunction "5_5") (pintype "passive"))
      (node (ref "J29") (pin "6") (pinfunction "6_6") (pintype "passive"))
      (node (ref "J29") (pin "7") (pinfunction "7_7") (pintype "passive"))
    )
    (net (code "30") (name "Net-(J30-Pad1)") (class "Default")
      (node (ref "J30") (pin "1") (pinfunction "1_1") (pintype "passive"))
      (node (ref "J30") (pin "2") (pinfunction "2_2") (pintype "passive"))
      (node (ref "J30") (pin "3") (pinfunction "3_3") (pintype "passive"))
      (node (ref "J30") (pin "4") (pinfunction "4_4") (pintype "passive"))
      (node (ref "J30") (pin "5") (pinfunction "5_5") (pintype "passive"))
      (node (ref "J30") (pin "6") (pinfunction "6_6") (pintype "passive"))
      (node (ref "J30") (pin "7") (pinfunction "7_7") (pintype "passive"))
    )
    (net (code "31") (name "Net-(J31-Pad1)") (class "Default")
      (node (ref "J31") (pin "1") (pinfunction "1_1") (pintype "passive"))
      (node (ref "J31") (pin "2") (pinfunction "2_2") (pintype "passive"))
      (node (ref "J31") (pin "3") (pinfunction "3_3") (pintype "passive"))
      (node (ref "J31") (pin "4") (pinfunction "4_4") (pintype "passive"))
      (node (ref "J31") (pin "5") (pinfunction "5_5") (pintype "passive"))
    )
    (net (code "32") (name "Net-(J32-Pad1)") (class "Default")
      (node (ref "J32") (pin "1") (pinfunction "1_1") (pintype "passive"))
      (node (ref "J32") (pin "2") (pinfunction "2_2") (pintype "passive"))
      (node (ref "J32") (pin "3") (pinfunction "3_3") (pintype "passive"))
    )
    (net (code "33") (name "Net-(JP1-1)") (class "Default")
      (node (ref "J38") (pin "1") (pinfunction "1_1") (pintype "passive"))
      (node (ref "JP1") (pin "P$1") (pinfunction "1_P$1") (pintype "passive"))
    )
    (net (code "34") (name "Net-(JP2-1)") (class "Default")
      (node (ref "J37") (pin "1") (pinfunction "1_1") (pintype "passive"))
      (node (ref "JP2") (pin "P$1") (pinfunction "1_P$1") (pintype "passive"))
    )
    (net (code "35") (name "Net-(JP3-1)") (class "Default")
      (node (ref "J36") (pin "1") (pinfunction "1_1") (pintype "passive"))
      (node (ref "JP3") (pin "P$1") (pinfunction "1_P$1") (pintype "passive"))
    )
    (net (code "36") (name "VCC") (class "Default")
      (node (ref "DC") (pin "1") (pinfunction "VIN_1") (pintype "passive"))
      (node (ref "U2") (pin "1") (pinfunction "IN_1") (pintype "input"))
      (node (ref "U2") (pin "3") (pinfunction "EN_3") (pintype "input"))
      (node (ref "X1") (pin "VBUS") (pinfunction "VBUS_VBUS") (pintype "power_in"))
    )
    (net (code "37") (name "VDD") (class "Default")
      (node (ref "DC") (pin "3") (pinfunction "VOUT_3") (pintype "passive"))
      (node (ref "PAD10") (pin "1") (pinfunction "P_1") (pintype "passive"))
      (node (ref "PAD11") (pin "1") (pinfunction "P_1") (pintype "passive"))
      (node (ref "PAD12") (pin "1") (pinfunction "P_1") (pintype "passive"))
      (node (ref "PAD13") (pin "1") (pinfunction "P_1") (pintype "passive"))
      (node (ref "PAD14") (pin "1") (pinfunction "P_1") (pintype "passive"))
      (node (ref "PAD15") (pin "1") (pinfunction "P_1") (pintype "passive"))
      (node (ref "PAD16") (pin "1") (pinfunction "P_1") (pintype "passive"))
      (node (ref "PAD18") (pin "1") (pinfunction "P_1") (pintype "passive"))
      (node (ref "PAD19") (pin "1") (pinfunction "P_1") (pintype "passive"))
      (node (ref "PAD20") (pin "1") (pinfunction "P_1") (pintype "passive"))
      (node (ref "PAD21") (pin "1") (pinfunction "P_1") (pintype "passive"))
      (node (ref "PAD442") (pin "1") (pinfunction "P_1") (pintype "passive"))
      (node (ref "PAD443") (pin "1") (pinfunction "P_1") (pintype "passive"))
      (node (ref "PAD444") (pin "1") (pinfunction "P_1") (pintype "passive"))
      (node (ref "PAD445") (pin "1") (pinfunction "P_1") (pintype "passive"))
      (node (ref "PAD446") (pin "1") (pinfunction "P_1") (pintype "passive"))
      (node (ref "PAD447") (pin "1") (pinfunction "P_1") (pintype "passive"))
      (node (ref "PAD448") (pin "1") (pinfunction "P_1") (pintype "passive"))
      (node (ref "PAD449") (pin "1") (pinfunction "P_1") (pintype "passive"))
      (node (ref "PAD450") (pin "1") (pinfunction "P_1") (pintype "passive"))
      (node (ref "PAD451") (pin "1") (pinfunction "P_1") (pintype "passive"))
      (node (ref "PAD452") (pin "1") (pinfunction "P_1") (pintype "passive"))
      (node (ref "PAD453") (pin "1") (pinfunction "P_1") (pintype "passive"))
      (node (ref "PAD454") (pin "1") (pinfunction "P_1") (pintype "passive"))
      (node (ref "PAD455") (pin "1") (pinfunction "P_1") (pintype "passive"))
      (node (ref "PAD456") (pin "1") (pinfunction "P_1") (pintype "passive"))
      (node (ref "PAD459") (pin "1") (pinfunction "P_1") (pintype "passive"))
      (node (ref "PAD460") (pin "1") (pinfunction "P_1") (pintype "passive"))
      (node (ref "PAD461") (pin "1") (pinfunction "P_1") (pintype "passive"))
      (node (ref "PAD462") (pin "1") (pinfunction "P_1") (pintype "passive"))
      (node (ref "PAD5") (pin "1") (pinfunction "P_1") (pintype "passive"))
      (node (ref "PAD6") (pin "1") (pinfunction "P_1") (pintype "passive"))
      (node (ref "PAD7") (pin "1") (pinfunction "P_1") (pintype "passive"))
      (node (ref "PAD8") (pin "1") (pinfunction "P_1") (pintype "passive"))
      (node (ref "PAD9") (pin "1") (pinfunction "P_1") (pintype "passive"))
      (node (ref "U2") (pin "5") (pinfunction "OUT_5") (pintype "passive"))
    )
    (net (code "38") (name "unconnected-(U2-BP-Pad4)") (class "Default")
      (node (ref "U2") (pin "4") (pinfunction "BP_4") (pintype "input"))
    )
    (net (code "39") (name "unconnected-(X1-PadD+)") (class "Default")
      (node (ref "X1") (pin "D+") (pinfunction "D+_D+") (pintype "bidirectional"))
    )
    (net (code "40") (name "unconnected-(X1-PadD-)") (class "Default")
      (node (ref "X1") (pin "D-") (pinfunction "D-_D-") (pintype "bidirectional"))
    )
    (net (code "41") (name "unconnected-(X1-PadID)") (class "Default")
      (node (ref "X1") (pin "ID") (pinfunction "ID_ID") (pintype "bidirectional"))
    )
  )
)
